# Schematic_v38.net
KiCad netlist of a schematic drawn in EAGLE
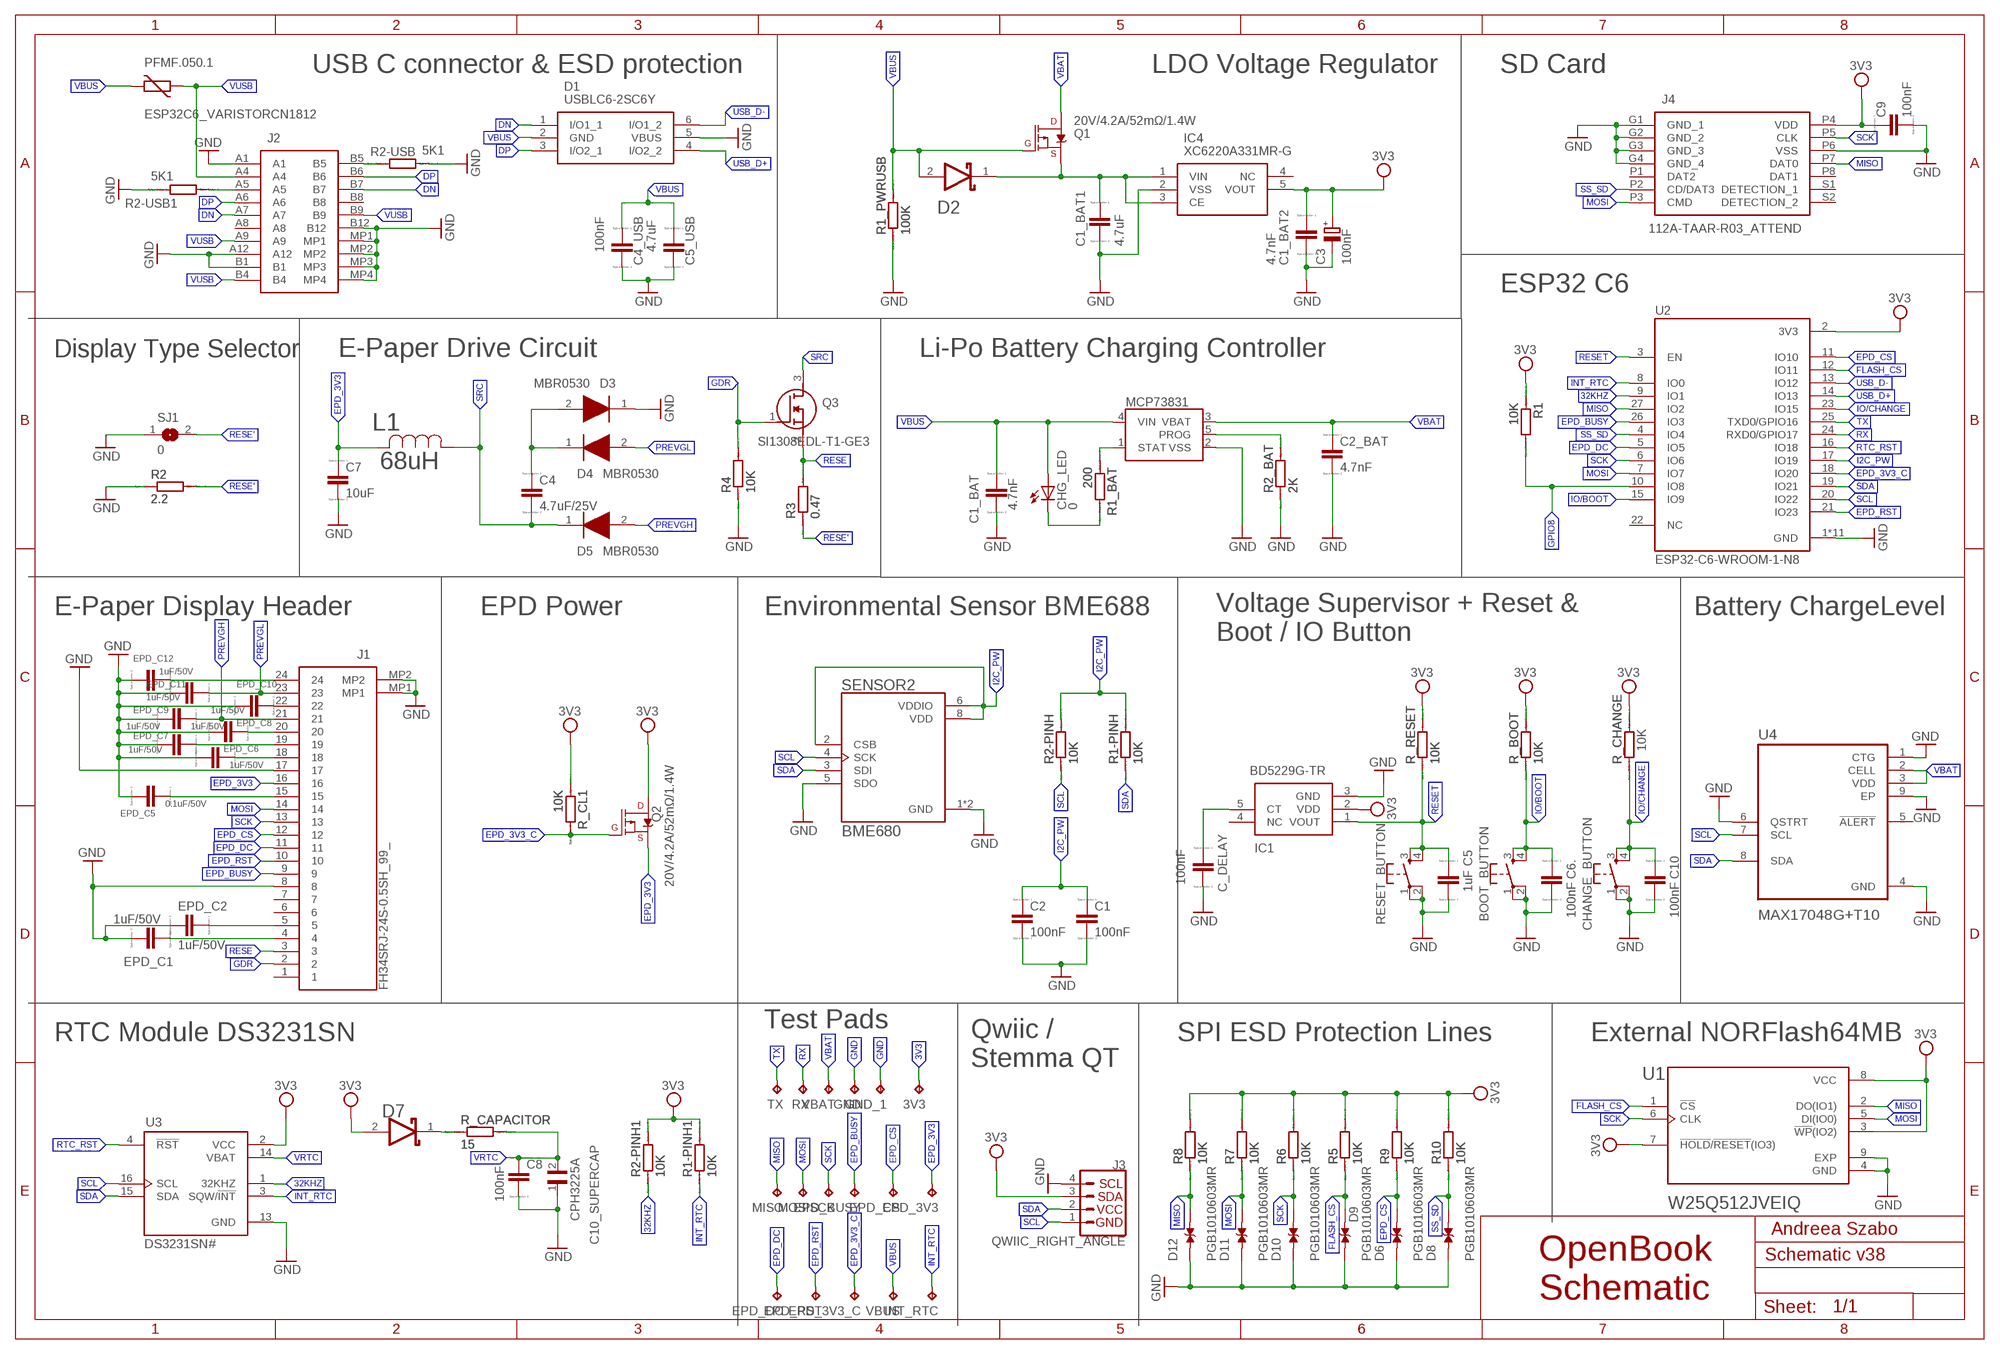
[diagram p0: schematic, sheet 1]

(export (version "E")
  (design (tool "Eeschema 10.0.6"))
  (components
    (comp (ref "3V3")
      (value "TPTP20R")
      (footprint "eagle-import:TP20R")
      (libsource (lib "eagle-import") (part "TPTP20R"))
    )
    (comp (ref "BOOT_BUTTON")
      (value "BUTTON_CUSYOMV1")
      (footprint "eagle-import:MYBUTTON")
      (libsource (lib "eagle-import") (part "BUTTON_CUSYOMV1"))
    )
    (comp (ref "C1")
      (value "100nF")
      (footprint "eagle-import:ESP32_WROVER_EAGLE-LTSPICE_C0402")
      (libsource (lib "eagle-import") (part "EAGLE-LTSPICE_CC0402"))
    )
    (comp (ref "C1_BAT")
      (value "4.7nF")
      (footprint "eagle-import:ESP32_WROVER_EAGLE-LTSPICE_C0402")
      (libsource (lib "eagle-import") (part "EAGLE-LTSPICE_CC0402"))
    )
    (comp (ref "C1_BAT1")
      (value "4.7uF")
      (footprint "eagle-import:ESP32_WROVER_EAGLE-LTSPICE_C0402")
      (libsource (lib "eagle-import") (part "EAGLE-LTSPICE_CC0402"))
    )
    (comp (ref "C1_BAT2")
      (value "4.7nF")
      (footprint "eagle-import:ESP32_WROVER_EAGLE-LTSPICE_C0402")
      (libsource (lib "eagle-import") (part "EAGLE-LTSPICE_CC0402"))
    )
    (comp (ref "C2")
      (value "100nF")
      (footprint "eagle-import:ESP32_WROVER_EAGLE-LTSPICE_C0402")
      (libsource (lib "eagle-import") (part "EAGLE-LTSPICE_CC0402"))
    )
    (comp (ref "C2_BAT")
      (value "4.7nF")
      (footprint "eagle-import:ESP32_WROVER_EAGLE-LTSPICE_C0402")
      (libsource (lib "eagle-import") (part "EAGLE-LTSPICE_CC0402"))
    )
    (comp (ref "C3")
      (value "100nF")
      (footprint "eagle-import:RCL_CT3528")
      (libsource (lib "eagle-import") (part "RCL_CPOL-EUCT3528"))
    )
    (comp (ref "C4")
      (value "4.7uF/25V")
      (footprint "eagle-import:ESP32_WROVER_EAGLE-LTSPICE_C0402")
      (libsource (lib "eagle-import") (part "EAGLE-LTSPICE_CC0402"))
    )
    (comp (ref "C4_USB")
      (value "100nF")
      (footprint "eagle-import:ESP32_WROVER_EAGLE-LTSPICE_C0402")
      (libsource (lib "eagle-import") (part "EAGLE-LTSPICE_CC0402"))
    )
    (comp (ref "C5")
      (value "1uF")
      (footprint "eagle-import:ESP32_WROVER_EAGLE-LTSPICE_C0402")
      (libsource (lib "eagle-import") (part "EAGLE-LTSPICE_CC0402"))
    )
    (comp (ref "C5_USB")
      (value "4.7uF")
      (footprint "eagle-import:ESP32_WROVER_EAGLE-LTSPICE_C0402")
      (libsource (lib "eagle-import") (part "EAGLE-LTSPICE_CC0402"))
    )
    (comp (ref "C6.")
      (value "100nF")
      (footprint "eagle-import:ESP32_WROVER_EAGLE-LTSPICE_C0402")
      (libsource (lib "eagle-import") (part "EAGLE-LTSPICE_CC0402"))
    )
    (comp (ref "C7")
      (value "10uF")
      (footprint "eagle-import:ESP32_WROVER_EAGLE-LTSPICE_C0402")
      (libsource (lib "eagle-import") (part "EAGLE-LTSPICE_CC0402"))
    )
    (comp (ref "C8")
      (value "100nF")
      (footprint "eagle-import:ESP32_WROVER_EAGLE-LTSPICE_C0402")
      (libsource (lib "eagle-import") (part "EAGLE-LTSPICE_CC0402"))
    )
    (comp (ref "C9")
      (value "100nF")
      (footprint "eagle-import:ESP32_WROVER_EAGLE-LTSPICE_C0402")
      (libsource (lib "eagle-import") (part "EAGLE-LTSPICE_CC0402"))
    )
    (comp (ref "C10")
      (value "100nF")
      (footprint "eagle-import:ESP32_WROVER_EAGLE-LTSPICE_C0402")
      (libsource (lib "eagle-import") (part "EAGLE-LTSPICE_CC0402"))
    )
    (comp (ref "C10_SUPERCAP")
      (value "CPH3225A")
      (footprint "eagle-import:CAPCP3225X100N")
      (fields (field (name "MF") "Seiko Instruments"))
      (libsource (lib "eagle-import") (part "CPH3225A"))
    )
    (comp (ref "CHANGE_BUTTON")
      (value "BUTTON_CUSYOMV1")
      (footprint "eagle-import:MYBUTTON")
      (libsource (lib "eagle-import") (part "BUTTON_CUSYOMV1"))
    )
    (comp (ref "CHG_LED")
      (value "0")
      (footprint "eagle-import:ADAFRUIT_CHIP-LED0603")
      (libsource (lib "eagle-import") (part "ADAFRUIT_LEDCHIP-LED0603"))
    )
    (comp (ref "C_DELAY")
      (value "100nF")
      (footprint "eagle-import:ESP32_WROVER_EAGLE-LTSPICE_C0402")
      (libsource (lib "eagle-import") (part "EAGLE-LTSPICE_CC0402"))
    )
    (comp (ref "D1")
      (value "USBLC6-2SC6Y")
      (footprint "eagle-import:SOT95P280X145-6N")
      (fields (field (name "MF") "STMicroelectronics"))
      (libsource (lib "eagle-import") (part "USBLC6-2SC6Y"))
    )
    (comp (ref "D2")
      (value "ESP32_WROVER_AVX---SD0805S020S1R0_AVX_SD0805S020S1R0_0_0AVX_SD0805S020S1R0_0_0")
      (footprint "eagle-import:ESP32_WROVER_AVX---SD0805S020S1R0_AVX_SD0805S020S1R0_0")
      (fields
        (field (name "DIGIKEY_PART_NUMBER") "478-7800-1-ND")
        (field (name "MF") "AVX")
        (field (name "MOUSER_PART_NUMBER") "581-SD0805S020S1R0")
      )
      (libsource (lib "eagle-import") (part "ESP32_WROVER_AVX---SD0805S020S1R0_AVX_SD0805S020S1R0_0_0AVX_SD0805S020S1R0_0_0"))
    )
    (comp (ref "D3")
      (value "MBR0530")
      (footprint "eagle-import:SOD3716X135N")
      (fields (field (name "MF") "ON Semiconductor"))
      (libsource (lib "eagle-import") (part "MBR0530"))
    )
    (comp (ref "D4")
      (value "MBR0530")
      (footprint "eagle-import:SOD3716X135N")
      (fields (field (name "MF") "ON Semiconductor"))
      (libsource (lib "eagle-import") (part "MBR0530"))
    )
    (comp (ref "D5")
      (value "MBR0530")
      (footprint "eagle-import:SOD3716X135N")
      (fields (field (name "MF") "ON Semiconductor"))
      (libsource (lib "eagle-import") (part "MBR0530"))
    )
    (comp (ref "D6")
      (value "PGB1010603MR")
      (footprint "eagle-import:DIOC1608X36N")
      (fields (field (name "MF") "Littelfuse Inc."))
      (libsource (lib "eagle-import") (part "PGB1010603MR"))
    )
    (comp (ref "D7")
      (value "SD0805S020S1R0")
      (footprint "eagle-import:ESP32_WROVER_AVX---SD0805S020S1R0_AVX_SD0805S020S1R0_0")
      (fields
        (field (name "DIGIKEY_PART_NUMBER") "478-7800-1-ND")
        (field (name "MF") "AVX")
        (field (name "MOUSER_PART_NUMBER") "581-SD0805S020S1R0")
      )
      (libsource (lib "eagle-import") (part "ESP32_WROVER_AVX---SD0805S020S1R0_AVX_SD0805S020S1R0_0_0AVX_SD0805S020S1R0_0_0"))
    )
    (comp (ref "D8")
      (value "PGB1010603MR")
      (footprint "eagle-import:DIOC1608X36N")
      (fields (field (name "MF") "Littelfuse Inc."))
      (libsource (lib "eagle-import") (part "PGB1010603MR"))
    )
    (comp (ref "D9")
      (value "PGB1010603MR")
      (footprint "eagle-import:DIOC1608X36N")
      (fields (field (name "MF") "Littelfuse Inc."))
      (libsource (lib "eagle-import") (part "PGB1010603MR"))
    )
    (comp (ref "D10")
      (value "PGB1010603MR")
      (footprint "eagle-import:DIOC1608X36N")
      (fields (field (name "MF") "Littelfuse Inc."))
      (libsource (lib "eagle-import") (part "PGB1010603MR"))
    )
    (comp (ref "D11")
      (value "PGB1010603MR")
      (footprint "eagle-import:DIOC1608X36N")
      (fields (field (name "MF") "Littelfuse Inc."))
      (libsource (lib "eagle-import") (part "PGB1010603MR"))
    )
    (comp (ref "D12")
      (value "PGB1010603MR")
      (footprint "eagle-import:DIOC1608X36N")
      (fields (field (name "MF") "Littelfuse Inc."))
      (libsource (lib "eagle-import") (part "PGB1010603MR"))
    )
    (comp (ref "EPD_3V3")
      (value "TPTP20R")
      (footprint "eagle-import:TP20R")
      (libsource (lib "eagle-import") (part "TPTP20R"))
    )
    (comp (ref "EPD_3V3_C")
      (value "TPTP20R")
      (footprint "eagle-import:TP20R")
      (libsource (lib "eagle-import") (part "TPTP20R"))
    )
    (comp (ref "EPD_BUSY")
      (value "TPTP20R")
      (footprint "eagle-import:TP20R")
      (libsource (lib "eagle-import") (part "TPTP20R"))
    )
    (comp (ref "EPD_C1")
      (value "1uF/50V")
      (footprint "eagle-import:ESP32_WROVER_EAGLE-LTSPICE_C0402")
      (libsource (lib "eagle-import") (part "EAGLE-LTSPICE_CC0402"))
    )
    (comp (ref "EPD_C2")
      (value "1uF/50V")
      (footprint "eagle-import:ESP32_WROVER_EAGLE-LTSPICE_C0402")
      (libsource (lib "eagle-import") (part "EAGLE-LTSPICE_CC0402"))
    )
    (comp (ref "EPD_C5")
      (value "0.1uF/50V")
      (footprint "eagle-import:ESP32_WROVER_EAGLE-LTSPICE_C0402")
      (libsource (lib "eagle-import") (part "EAGLE-LTSPICE_CC0402"))
    )
    (comp (ref "EPD_C6")
      (value "1uF/50V")
      (footprint "eagle-import:ESP32_WROVER_EAGLE-LTSPICE_C0402")
      (libsource (lib "eagle-import") (part "EAGLE-LTSPICE_CC0402"))
    )
    (comp (ref "EPD_C7")
      (value "1uF/50V")
      (footprint "eagle-import:ESP32_WROVER_EAGLE-LTSPICE_C0402")
      (libsource (lib "eagle-import") (part "EAGLE-LTSPICE_CC0402"))
    )
    (comp (ref "EPD_C8")
      (value "1uF/50V")
      (footprint "eagle-import:ESP32_WROVER_EAGLE-LTSPICE_C0402")
      (libsource (lib "eagle-import") (part "EAGLE-LTSPICE_CC0402"))
    )
    (comp (ref "EPD_C9")
      (value "1uF/50V")
      (footprint "eagle-import:ESP32_WROVER_EAGLE-LTSPICE_C0402")
      (libsource (lib "eagle-import") (part "EAGLE-LTSPICE_CC0402"))
    )
    (comp (ref "EPD_C10")
      (value "1uF/50V")
      (footprint "eagle-import:ESP32_WROVER_EAGLE-LTSPICE_C0402")
      (libsource (lib "eagle-import") (part "EAGLE-LTSPICE_CC0402"))
    )
    (comp (ref "EPD_C11")
      (value "1uF/50V")
      (footprint "eagle-import:ESP32_WROVER_EAGLE-LTSPICE_C0402")
      (libsource (lib "eagle-import") (part "EAGLE-LTSPICE_CC0402"))
    )
    (comp (ref "EPD_C12")
      (value "1uF/50V")
      (footprint "eagle-import:ESP32_WROVER_EAGLE-LTSPICE_C0402")
      (libsource (lib "eagle-import") (part "EAGLE-LTSPICE_CC0402"))
    )
    (comp (ref "EPD_CS")
      (value "TPTP20R")
      (footprint "eagle-import:TP20R")
      (libsource (lib "eagle-import") (part "TPTP20R"))
    )
    (comp (ref "EPD_DC")
      (value "TPTP20R")
      (footprint "eagle-import:TP20R")
      (libsource (lib "eagle-import") (part "TPTP20R"))
    )
    (comp (ref "EPD_RST")
      (value "TPTP20R")
      (footprint "eagle-import:TP20R")
      (libsource (lib "eagle-import") (part "TPTP20R"))
    )
    (comp (ref "GND")
      (value "TPTP20R")
      (footprint "eagle-import:TP20R")
      (libsource (lib "eagle-import") (part "TPTP20R"))
    )
    (comp (ref "GND_1")
      (value "TPTP20R")
      (footprint "eagle-import:TP20R")
      (libsource (lib "eagle-import") (part "TPTP20R"))
    )
    (comp (ref "IC1")
      (value "BD5229G-TR")
      (footprint "eagle-import:SOT95P280X125-5N")
      (fields (field (name "MOUSER_PART_NUMBER") "755-BD5229G-TR"))
      (libsource (lib "eagle-import") (part "BD5229G-TR"))
    )
    (comp (ref "IC4")
      (value "XC6220A331MR-G")
      (footprint "eagle-import:SOT95P280X120-5N")
      (fields (field (name "MOUSER_PART_NUMBER") "865-XC6220A331MR-G"))
      (libsource (lib "eagle-import") (part "XC6220A331MR-G"))
    )
    (comp (ref "INT_RTC")
      (value "TPTP20R")
      (footprint "eagle-import:TP20R")
      (libsource (lib "eagle-import") (part "TPTP20R"))
    )
    (comp (ref "J1")
      (value "FH34SRJ-24S-0.5SH_99_")
      (footprint "eagle-import:FH34SRJ24S05SH99")
      (fields
        (field (name "MANUFACTURER_PART_NUMBER") "FH34SRJ-24S-0.5SH(99)")
        (field (name "MOUSER_PART_NUMBER") "798-FH34SRJ24S05SH99")
      )
      (libsource (lib "eagle-import") (part "FH34SRJ-24S-0.5SH_99_"))
    )
    (comp (ref "J2")
      (value "SAMACSYS_PARTS_USB4110-GF-A")
      (footprint "eagle-import:SAMACSYS_PARTS_USB4110GFA")
      (fields
        (field (name "MANUFACTURER_PART_NUMBER") "USB4110-GF-A")
        (field (name "MOUSER_PART_NUMBER") "640-USB4110-GF-A")
      )
      (libsource (lib "eagle-import") (part "SAMACSYS_PARTS_USB4110-GF-A"))
    )
    (comp (ref "J3")
      (value "QWIIC_RIGHT_ANGLE")
      (footprint "eagle-import:JST04_1MM_RA")
      (libsource (lib "eagle-import") (part "QWIIC_CONNECTORJS-1MM"))
    )
    (comp (ref "J4")
      (value "112A-TAAR-R03_ATTEND")
      (footprint "eagle-import:112ATAARR03ATTEND")
      (fields (field (name "MANUFACTURER_PART_NUMBER") "112A-TAAR-R03 ATTEND"))
      (libsource (lib "eagle-import") (part "112A-TAAR-R03_ATTEND"))
    )
    (comp (ref "L1")
      (value "68uH")
      (footprint "eagle-import:IND_4828-WE-TPC_WRE")
      (fields
        (field (name "MANUFACTURER_PART_NUMBER") "744043680")
        (field (name "COPYRIGHT") "Copyright (C) 2024 Ultra Librarian. All rights reserved.")
      )
      (libsource (lib "eagle-import") (part "744043680IND_4828-WE-TPC_WRE"))
    )
    (comp (ref "MCP73831")
      (value "MCP73831")
      (footprint "eagle-import:ESP32_WROVER_SPARKFUN-IC-POWER_SOT23-5")
      (libsource (lib "eagle-import") (part "ESP32_WROVER_SPARKFUN-IC-POWER_MCP73831"))
    )
    (comp (ref "MISO")
      (value "TPTP20R")
      (footprint "eagle-import:TP20R")
      (libsource (lib "eagle-import") (part "TPTP20R"))
    )
    (comp (ref "MOSI")
      (value "TPTP20R")
      (footprint "eagle-import:TP20R")
      (libsource (lib "eagle-import") (part "TPTP20R"))
    )
    (comp (ref "PFMF.050.1")
      (value "ESP32C6_VARISTORCN1812")
      (footprint "eagle-import:ESP32C6_VARISTOR_CT_CN1812")
      (libsource (lib "eagle-import") (part "ESP32C6_VARISTORCN1812"))
    )
    (comp (ref "Q1")
      (value "20V/4.2A/52mΩ/1.4W")
      (footprint "eagle-import:ESP32_WROVER_SPARKFUN-DISCRETESEMI_SOT23-3")
      (libsource (lib "eagle-import") (part "ESP32_WROVER_SPARKFUN-DISCRETESEMI_MOSFET_PCH-DMG2305UX-7"))
    )
    (comp (ref "Q2")
      (value "20V/4.2A/52mΩ/1.4W")
      (footprint "eagle-import:ESP32_WROVER_SPARKFUN-DISCRETESEMI_SOT23-3")
      (libsource (lib "eagle-import") (part "ESP32_WROVER_SPARKFUN-DISCRETESEMI_MOSFET_PCH-DMG2305UX-7"))
    )
    (comp (ref "Q3")
      (value "SI1308EDL-T1-GE3")
      (footprint "eagle-import:SOT65P210X110-3N")
      (fields (field (name "MF") "Vishay Siliconix"))
      (libsource (lib "eagle-import") (part "SI1308EDL-T1-GE3"))
    )
    (comp (ref "R1")
      (value "10K")
      (footprint "eagle-import:ESP32_WROVER_EAGLE-LTSPICE_R0402")
      (libsource (lib "eagle-import") (part "ESP32_WROVER_EAGLE-LTSPICE_RR0402"))
    )
    (comp (ref "R1-PINH")
      (value "10K")
      (footprint "eagle-import:ESP32_WROVER_EAGLE-LTSPICE_R0402")
      (libsource (lib "eagle-import") (part "ESP32_WROVER_EAGLE-LTSPICE_RR0402"))
    )
    (comp (ref "R1-PINH1")
      (value "10K")
      (footprint "eagle-import:ESP32_WROVER_EAGLE-LTSPICE_R0402")
      (libsource (lib "eagle-import") (part "ESP32_WROVER_EAGLE-LTSPICE_RR0402"))
    )
    (comp (ref "R1_BAT")
      (value "200")
      (footprint "eagle-import:ESP32_WROVER_EAGLE-LTSPICE_R0402")
      (libsource (lib "eagle-import") (part "ESP32_WROVER_EAGLE-LTSPICE_RR0402"))
    )
    (comp (ref "R1_PWRUSB")
      (value "100K")
      (footprint "eagle-import:ESP32_WROVER_EAGLE-LTSPICE_R0402")
      (libsource (lib "eagle-import") (part "ESP32_WROVER_EAGLE-LTSPICE_RR0402"))
    )
    (comp (ref "R2")
      (value "2.2")
      (footprint "eagle-import:ESP32_WROVER_EAGLE-LTSPICE_R0402")
      (libsource (lib "eagle-import") (part "ESP32_WROVER_EAGLE-LTSPICE_RR0402"))
    )
    (comp (ref "R2-PINH")
      (value "10K")
      (footprint "eagle-import:ESP32_WROVER_EAGLE-LTSPICE_R0402")
      (libsource (lib "eagle-import") (part "ESP32_WROVER_EAGLE-LTSPICE_RR0402"))
    )
    (comp (ref "R2-PINH1")
      (value "10K")
      (footprint "eagle-import:ESP32_WROVER_EAGLE-LTSPICE_R0402")
      (libsource (lib "eagle-import") (part "ESP32_WROVER_EAGLE-LTSPICE_RR0402"))
    )
    (comp (ref "R2-USB")
      (value "5K1")
      (footprint "eagle-import:ESP32_WROVER_EAGLE-LTSPICE_R0402")
      (libsource (lib "eagle-import") (part "ESP32_WROVER_EAGLE-LTSPICE_RR0402"))
    )
    (comp (ref "R2-USB1")
      (value "5K1")
      (footprint "eagle-import:ESP32_WROVER_EAGLE-LTSPICE_R0402")
      (libsource (lib "eagle-import") (part "ESP32_WROVER_EAGLE-LTSPICE_RR0402"))
    )
    (comp (ref "R2_BAT")
      (value "2K")
      (footprint "eagle-import:ESP32_WROVER_EAGLE-LTSPICE_R0402")
      (libsource (lib "eagle-import") (part "ESP32_WROVER_EAGLE-LTSPICE_RR0402"))
    )
    (comp (ref "R3")
      (value "0.47")
      (footprint "eagle-import:ESP32_WROVER_EAGLE-LTSPICE_R0402")
      (libsource (lib "eagle-import") (part "ESP32_WROVER_EAGLE-LTSPICE_RR0402"))
    )
    (comp (ref "R4")
      (value "10K")
      (footprint "eagle-import:ESP32_WROVER_EAGLE-LTSPICE_R0402")
      (libsource (lib "eagle-import") (part "ESP32_WROVER_EAGLE-LTSPICE_RR0402"))
    )
    (comp (ref "R5")
      (value "10K")
      (footprint "eagle-import:ESP32_WROVER_EAGLE-LTSPICE_R0402")
      (libsource (lib "eagle-import") (part "ESP32_WROVER_EAGLE-LTSPICE_RR0402"))
    )
    (comp (ref "R6")
      (value "10K")
      (footprint "eagle-import:ESP32_WROVER_EAGLE-LTSPICE_R0402")
      (libsource (lib "eagle-import") (part "ESP32_WROVER_EAGLE-LTSPICE_RR0402"))
    )
    (comp (ref "R7")
      (value "10K")
      (footprint "eagle-import:ESP32_WROVER_EAGLE-LTSPICE_R0402")
      (libsource (lib "eagle-import") (part "ESP32_WROVER_EAGLE-LTSPICE_RR0402"))
    )
    (comp (ref "R8")
      (value "10K")
      (footprint "eagle-import:ESP32_WROVER_EAGLE-LTSPICE_R0402")
      (libsource (lib "eagle-import") (part "ESP32_WROVER_EAGLE-LTSPICE_RR0402"))
    )
    (comp (ref "R9")
      (value "10K")
      (footprint "eagle-import:ESP32_WROVER_EAGLE-LTSPICE_R0402")
      (libsource (lib "eagle-import") (part "ESP32_WROVER_EAGLE-LTSPICE_RR0402"))
    )
    (comp (ref "R10")
      (value "10K")
      (footprint "eagle-import:ESP32_WROVER_EAGLE-LTSPICE_R0402")
      (libsource (lib "eagle-import") (part "ESP32_WROVER_EAGLE-LTSPICE_RR0402"))
    )
    (comp (ref "RESET_BUTTON")
      (value "BUTTON_CUSYOMV1")
      (footprint "eagle-import:MYBUTTON")
      (libsource (lib "eagle-import") (part "BUTTON_CUSYOMV1"))
    )
    (comp (ref "RX")
      (value "TPTP20R")
      (footprint "eagle-import:TP20R")
      (libsource (lib "eagle-import") (part "TPTP20R"))
    )
    (comp (ref "R_BOOT")
      (value "10K")
      (footprint "eagle-import:ESP32_WROVER_EAGLE-LTSPICE_R0402")
      (libsource (lib "eagle-import") (part "ESP32_WROVER_EAGLE-LTSPICE_RR0402"))
    )
    (comp (ref "R_CAPACITOR")
      (value "15")
      (footprint "eagle-import:ESP32_WROVER_EAGLE-LTSPICE_R0402")
      (libsource (lib "eagle-import") (part "ESP32_WROVER_EAGLE-LTSPICE_RR0402"))
    )
    (comp (ref "R_CHANGE")
      (value "10K")
      (footprint "eagle-import:ESP32_WROVER_EAGLE-LTSPICE_R0402")
      (libsource (lib "eagle-import") (part "ESP32_WROVER_EAGLE-LTSPICE_RR0402"))
    )
    (comp (ref "R_CL1")
      (value "10K")
      (footprint "eagle-import:ESP32_WROVER_EAGLE-LTSPICE_R0402")
      (libsource (lib "eagle-import") (part "ESP32_WROVER_EAGLE-LTSPICE_RR0402"))
    )
    (comp (ref "R_RESET")
      (value "10K")
      (footprint "eagle-import:ESP32_WROVER_EAGLE-LTSPICE_R0402")
      (libsource (lib "eagle-import") (part "ESP32_WROVER_EAGLE-LTSPICE_RR0402"))
    )
    (comp (ref "SCK")
      (value "TPTP20R")
      (footprint "eagle-import:TP20R")
      (libsource (lib "eagle-import") (part "TPTP20R"))
    )
    (comp (ref "SENSOR2")
      (value "BME680")
      (footprint "eagle-import:ESP32_WROVER_BME680_PSON80P300X300X100-8N")
      (fields (field (name "MF") "Bosch Sensortec"))
      (libsource (lib "eagle-import") (part "ESP32_WROVER_BME680_BME680"))
    )
    (comp (ref "SJ1") (value "0") (footprint "eagle-import:SJ") (libsource (lib "eagle-import") (part "SJ")))
    (comp (ref "TX")
      (value "TPTP20R")
      (footprint "eagle-import:TP20R")
      (libsource (lib "eagle-import") (part "TPTP20R"))
    )
    (comp (ref "U1")
      (value "W25Q512JVEIQ")
      (footprint "eagle-import:SON127P600X800X80-9N")
      (fields (field (name "MF") "Winbond Electronics"))
      (libsource (lib "eagle-import") (part "W25Q512JVEIQ"))
    )
    (comp (ref "U2")
      (value "ESP32-C6-WROOM-1-N8")
      (footprint "eagle-import:XCVR_ESP32-C6-WROOM-1-N8")
      (fields (field (name "MF") "Espressif Systems"))
      (libsource (lib "eagle-import") (part "ESP32-C6-WROOM-1-N8"))
    )
    (comp (ref "U3")
      (value "DS3231SN#")
      (footprint "eagle-import:SOIC127P1032X265-16N")
      (fields (field (name "MF") "Analog Devices"))
      (libsource (lib "eagle-import") (part "DS3231SN#"))
    )
    (comp (ref "U4")
      (value "MAX17048G+T10")
      (footprint "eagle-import:SON50P200X200X80-9N")
      (fields (field (name "MF") "Analog Devices"))
      (libsource (lib "eagle-import") (part "MAX17048G+T10"))
    )
    (comp (ref "VBAT")
      (value "TPTP20R")
      (footprint "eagle-import:TP20R")
      (libsource (lib "eagle-import") (part "TPTP20R"))
    )
    (comp (ref "VBUS")
      (value "TPTP20R")
      (footprint "eagle-import:TP20R")
      (libsource (lib "eagle-import") (part "TPTP20R"))
    )
  )
  (nets
    (net (code "1") (name "3V3") (class "Default")
      (node (ref "3V3") (pin "TP") (pinfunction "TP_TP") (pintype "input"))
      (node (ref "C1_BAT2") (pin "1") (pinfunction "1_1") (pintype "passive"))
      (node (ref "C3") (pin "+") (pinfunction "+_+") (pintype "passive"))
      (node (ref "C9") (pin "1") (pinfunction "1_1") (pintype "passive"))
      (node (ref "D7") (pin "2") (pinfunction "ANODE_2") (pintype "bidirectional"))
      (node (ref "IC1") (pin "2") (pinfunction "VDD_2") (pintype "bidirectional"))
      (node (ref "IC4") (pin "5") (pinfunction "VOUT_5") (pintype "bidirectional"))
      (node (ref "J3") (pin "3") (pinfunction "3_3") (pintype "passive"))
      (node (ref "J4") (pin "P4") (pinfunction "VDD_P4") (pintype "bidirectional"))
      (node (ref "Q2") (pin "3") (pinfunction "D_3") (pintype "bidirectional"))
      (node (ref "R1") (pin "1") (pinfunction "1_1") (pintype "passive"))
      (node (ref "R1-PINH1") (pin "2") (pinfunction "2_2") (pintype "passive"))
      (node (ref "R10") (pin "2") (pinfunction "2_2") (pintype "passive"))
      (node (ref "R2-PINH1") (pin "2") (pinfunction "2_2") (pintype "passive"))
      (node (ref "R5") (pin "2") (pinfunction "2_2") (pintype "passive"))
      (node (ref "R6") (pin "2") (pinfunction "2_2") (pintype "passive"))
      (node (ref "R7") (pin "2") (pinfunction "2_2") (pintype "passive"))
      (node (ref "R8") (pin "2") (pinfunction "2_2") (pintype "passive"))
      (node (ref "R9") (pin "2") (pinfunction "2_2") (pintype "passive"))
      (node (ref "R_BOOT") (pin "2") (pinfunction "2_2") (pintype "passive"))
      (node (ref "R_CHANGE") (pin "2") (pinfunction "2_2") (pintype "passive"))
      (node (ref "R_CL1") (pin "1") (pinfunction "1_1") (pintype "passive"))
      (node (ref "R_RESET") (pin "2") (pinfunction "2_2") (pintype "passive"))
      (node (ref "U1") (pin "3") (pinfunction "~{WP}(IO2)_3") (pintype "bidirectional"))
      (node (ref "U1") (pin "7") (pinfunction "~{HOLD}/~{RESET}(IO3)_7") (pintype "bidirectional"))
      (node (ref "U1") (pin "8") (pinfunction "VCC_8") (pintype "power_in"))
      (node (ref "U2") (pin "2") (pinfunction "3V3_2") (pintype "power_in"))
      (node (ref "U3") (pin "2") (pinfunction "VCC_2") (pintype "power_in"))
    )
    (net (code "2") (name "32KHZ") (class "Default")
      (node (ref "R2-PINH1") (pin "1") (pinfunction "1_1") (pintype "passive"))
      (node (ref "U2") (pin "9") (pinfunction "IO1_9") (pintype "bidirectional"))
      (node (ref "U3") (pin "1") (pinfunction "32KHZ_1") (pintype "output"))
    )
    (net (code "3") (name "DN") (class "Default")
      (node (ref "D1") (pin "1") (pinfunction "I/O1_1_1") (pintype "bidirectional"))
      (node (ref "J2") (pin "A7") (pinfunction "A7_A7") (pintype "bidirectional"))
      (node (ref "J2") (pin "B7") (pinfunction "B7_B7") (pintype "bidirectional"))
    )
    (net (code "4") (name "DP") (class "Default")
      (node (ref "D1") (pin "3") (pinfunction "I/O2_1_3") (pintype "bidirectional"))
      (node (ref "J2") (pin "A6") (pinfunction "A6_A6") (pintype "bidirectional"))
      (node (ref "J2") (pin "B6") (pinfunction "B6_B6") (pintype "bidirectional"))
    )
    (net (code "5") (name "EPD_3V3") (class "Default")
      (node (ref "C7") (pin "1") (pinfunction "1_1") (pintype "passive"))
      (node (ref "EPD_3V3") (pin "TP") (pinfunction "TP_TP") (pintype "input"))
      (node (ref "J1") (pin "16") (pinfunction "16_16") (pintype "bidirectional"))
      (node (ref "L1") (pin "2") (pinfunction "2_2") (pintype "passive"))
      (node (ref "Q2") (pin "2") (pinfunction "S_2") (pintype "bidirectional"))
    )
    (net (code "6") (name "EPD_3V3_C") (class "Default")
      (node (ref "EPD_3V3_C") (pin "TP") (pinfunction "TP_TP") (pintype "input"))
      (node (ref "Q2") (pin "1") (pinfunction "G_1") (pintype "bidirectional"))
      (node (ref "R_CL1") (pin "2") (pinfunction "2_2") (pintype "passive"))
      (node (ref "U2") (pin "18") (pinfunction "IO20_18") (pintype "bidirectional"))
    )
    (net (code "7") (name "EPD_BUSY") (class "Default")
      (node (ref "EPD_BUSY") (pin "TP") (pinfunction "TP_TP") (pintype "input"))
      (node (ref "J1") (pin "9") (pinfunction "9_9") (pintype "bidirectional"))
      (node (ref "U2") (pin "26") (pinfunction "IO3_26") (pintype "bidirectional"))
    )
    (net (code "8") (name "EPD_CS") (class "Default")
      (node (ref "D6") (pin "2") (pinfunction "2_2") (pintype "passive"))
      (node (ref "EPD_CS") (pin "TP") (pinfunction "TP_TP") (pintype "input"))
      (node (ref "J1") (pin "12") (pinfunction "12_12") (pintype "bidirectional"))
      (node (ref "R9") (pin "1") (pinfunction "1_1") (pintype "passive"))
      (node (ref "U2") (pin "11") (pinfunction "IO10_11") (pintype "bidirectional"))
    )
    (net (code "9") (name "EPD_DC") (class "Default")
      (node (ref "EPD_DC") (pin "TP") (pinfunction "TP_TP") (pintype "input"))
      (node (ref "J1") (pin "11") (pinfunction "11_11") (pintype "bidirectional"))
      (node (ref "U2") (pin "5") (pinfunction "IO5_5") (pintype "bidirectional"))
    )
    (net (code "10") (name "EPD_RST") (class "Default")
      (node (ref "EPD_RST") (pin "TP") (pinfunction "TP_TP") (pintype "input"))
      (node (ref "J1") (pin "10") (pinfunction "10_10") (pintype "bidirectional"))
      (node (ref "U2") (pin "21") (pinfunction "IO23_21") (pintype "bidirectional"))
    )
    (net (code "11") (name "FLASH_CS") (class "Default")
      (node (ref "D9") (pin "2") (pinfunction "2_2") (pintype "passive"))
      (node (ref "R5") (pin "1") (pinfunction "1_1") (pintype "passive"))
      (node (ref "U1") (pin "1") (pinfunction "~{CS}_1") (pintype "input"))
      (node (ref "U2") (pin "12") (pinfunction "IO11_12") (pintype "bidirectional"))
    )
    (net (code "12") (name "GDR") (class "Default")
      (node (ref "J1") (pin "2") (pinfunction "2_2") (pintype "bidirectional"))
      (node (ref "Q3") (pin "1") (pinfunction "G_1") (pintype "bidirectional"))
      (node (ref "R4") (pin "2") (pinfunction "2_2") (pintype "passive"))
    )
    (net (code "13") (name "GND") (class "Default")
      (node (ref "BOOT_BUTTON") (pin "1") (pinfunction "1_1") (pintype "passive"))
      (node (ref "BOOT_BUTTON") (pin "2") (pinfunction "2_2") (pintype "passive"))
      (node (ref "C1") (pin "2") (pinfunction "2_2") (pintype "passive"))
      (node (ref "C10") (pin "2") (pinfunction "2_2") (pintype "passive"))
      (node (ref "C10_SUPERCAP") (pin "1") (pinfunction "1_1") (pintype "passive"))
      (node (ref "C1_BAT") (pin "2") (pinfunction "2_2") (pintype "passive"))
      (node (ref "C1_BAT1") (pin "2") (pinfunction "2_2") (pintype "passive"))
      (node (ref "C1_BAT2") (pin "2") (pinfunction "2_2") (pintype "passive"))
      (node (ref "C2") (pin "2") (pinfunction "2_2") (pintype "passive"))
      (node (ref "C2_BAT") (pin "2") (pinfunction "2_2") (pintype "passive"))
      (node (ref "C3") (pin "-") (pinfunction "-_-") (pintype "passive"))
      (node (ref "C4_USB") (pin "2") (pinfunction "2_2") (pintype "passive"))
      (node (ref "C5") (pin "2") (pinfunction "2_2") (pintype "passive"))
      (node (ref "C5_USB") (pin "2") (pinfunction "2_2") (pintype "passive"))
      (node (ref "C6.") (pin "2") (pinfunction "2_2") (pintype "passive"))
      (node (ref "C7") (pin "2") (pinfunction "2_2") (pintype "passive"))
      (node (ref "C8") (pin "2") (pinfunction "2_2") (pintype "passive"))
      (node (ref "C9") (pin "2") (pinfunction "2_2") (pintype "passive"))
      (node (ref "CHANGE_BUTTON") (pin "1") (pinfunction "1_1") (pintype "passive"))
      (node (ref "CHANGE_BUTTON") (pin "2") (pinfunction "2_2") (pintype "passive"))
      (node (ref "C_DELAY") (pin "2") (pinfunction "2_2") (pintype "passive"))
      (node (ref "D1") (pin "5") (pinfunction "VBUS_5") (pintype "bidirectional"))
      (node (ref "D10") (pin "1") (pinfunction "1_1") (pintype "passive"))
      (node (ref "D11") (pin "1") (pinfunction "1_1") (pintype "passive"))
      (node (ref "D12") (pin "1") (pinfunction "1_1") (pintype "passive"))
      (node (ref "D3") (pin "1") (pinfunction "K_1") (pintype "bidirectional"))
      (node (ref "D6") (pin "1") (pinfunction "1_1") (pintype "passive"))
      (node (ref "D8") (pin "1") (pinfunction "1_1") (pintype "passive"))
      (node (ref "D9") (pin "1") (pinfunction "1_1") (pintype "passive"))
      (node (ref "EPD_C1") (pin "2") (pinfunction "2_2") (pintype "passive"))
      (node (ref "EPD_C10") (pin "2") (pinfunction "2_2") (pintype "passive"))
      (node (ref "EPD_C11") (pin "2") (pinfunction "2_2") (pintype "passive"))
      (node (ref "EPD_C12") (pin "2") (pinfunction "2_2") (pintype "passive"))
      (node (ref "EPD_C2") (pin "2") (pinfunction "2_2") (pintype "passive"))
      (node (ref "EPD_C5") (pin "2") (pinfunction "2_2") (pintype "passive"))
      (node (ref "EPD_C6") (pin "2") (pinfunction "2_2") (pintype "passive"))
      (node (ref "EPD_C7") (pin "2") (pinfunction "2_2") (pintype "passive"))
      (node (ref "EPD_C8") (pin "2") (pinfunction "2_2") (pintype "passive"))
      (node (ref "EPD_C9") (pin "2") (pinfunction "2_2") (pintype "passive"))
      (node (ref "GND") (pin "TP") (pinfunction "TP_TP") (pintype "input"))
      (node (ref "GND_1") (pin "TP") (pinfunction "TP_TP") (pintype "input"))
      (node (ref "IC1") (pin "3") (pinfunction "GND_3") (pintype "bidirectional"))
      (node (ref "IC4") (pin "2") (pinfunction "VSS_2") (pintype "bidirectional"))
      (node (ref "J1") (pin "17") (pinfunction "17_17") (pintype "bidirectional"))
      (node (ref "J1") (pin "8") (pinfunction "8_8") (pintype "bidirectional"))
      (node (ref "J1") (pin "MP1") (pinfunction "MP1_MP1") (pintype "bidirectional"))
      (node (ref "J1") (pin "MP2") (pinfunction "MP2_MP2") (pintype "bidirectional"))
      (node (ref "J2") (pin "A1") (pinfunction "A1_A1") (pintype "bidirectional"))
      (node (ref "J2") (pin "A12") (pinfunction "A12_A12") (pintype "bidirectional"))
      (node (ref "J2") (pin "B1") (pinfunction "B1_B1") (pintype "bidirectional"))
      (node (ref "J2") (pin "B12") (pinfunction "B12_B12") (pintype "bidirectional"))
      (node (ref "J2") (pin "MP1") (pinfunction "MP1_MP1") (pintype "bidirectional"))
      (node (ref "J2") (pin "MP2") (pinfunction "MP2_MP2") (pintype "bidirectional"))
      (node (ref "J2") (pin "MP3") (pinfunction "MP3_MP3") (pintype "bidirectional"))
      (node (ref "J2") (pin "MP4") (pinfunction "MP4_MP4") (pintype "bidirectional"))
      (node (ref "J3") (pin "4") (pinfunction "4_4") (pintype "passive"))
      (node (ref "J4") (pin "G1") (pinfunction "GND_1_G1") (pintype "bidirectional"))
      (node (ref "J4") (pin "G2") (pinfunction "GND_2_G2") (pintype "bidirectional"))
      (node (ref "J4") (pin "G3") (pinfunction "GND_3_G3") (pintype "bidirectional"))
      (node (ref "J4") (pin "G4") (pinfunction "GND_4_G4") (pintype "bidirectional"))
      (node (ref "J4") (pin "P6") (pinfunction "VSS_P6") (pintype "bidirectional"))
      (node (ref "MCP73831") (pin "2") (pinfunction "VSS_2") (pintype "power_in"))
      (node (ref "R1_PWRUSB") (pin "1") (pinfunction "1_1") (pintype "passive"))
      (node (ref "R2") (pin "1") (pinfunction "1_1") (pintype "passive"))
      (node (ref "R2-USB") (pin "2") (pinfunction "2_2") (pintype "passive"))
      (node (ref "R2-USB1") (pin "1") (pinfunction "1_1") (pintype "passive"))
      (node (ref "R2_BAT") (pin "1") (pinfunction "1_1") (pintype "passive"))
      (node (ref "R4") (pin "1") (pinfunction "1_1") (pintype "passive"))
      (node (ref "RESET_BUTTON") (pin "1") (pinfunction "1_1") (pintype "passive"))
      (node (ref "RESET_BUTTON") (pin "2") (pinfunction "2_2") (pintype "passive"))
      (node (ref "SENSOR2") (pin "1") (pinfunction "GND_1") (pintype "power_in"))
      (node (ref "SENSOR2") (pin "5") (pinfunction "SDO_5") (pintype "bidirectional"))
      (node (ref "SENSOR2") (pin "7") (pinfunction "GND_7") (pintype "power_in"))
      (node (ref "SJ1") (pin "1") (pinfunction "1_1") (pintype "passive"))
      (node (ref "U1") (pin "4") (pinfunction "GND_4") (pintype "power_in"))
      (node (ref "U1") (pin "9") (pinfunction "EXP_9") (pintype "passive"))
      (node (ref "U2") (pin "1") (pinfunction "GND_1") (pintype "power_in"))
      (node (ref "U2") (pin "28") (pinfunction "GND_28") (pintype "power_in"))
      (node (ref "U2") (pin "29_1") (pinfunction "GND_29_1") (pintype "power_in"))
      (node (ref "U2") (pin "29_2") (pinfunction "GND_29_2") (pintype "power_in"))
      (node (ref "U2") (pin "29_3") (pinfunction "GND_29_3") (pintype "power_in"))
      (node (ref "U2") (pin "29_4") (pinfunction "GND_29_4") (pintype "power_in"))
      (node (ref "U2") (pin "29_5") (pinfunction "GND_29_5") (pintype "power_in"))
      (node (ref "U2") (pin "29_6") (pinfunction "GND_29_6") (pintype "power_in"))
      (node (ref "U2") (pin "29_7") (pinfunction "GND_29_7") (pintype "power_in"))
      (node (ref "U2") (pin "29_8") (pinfunction "GND_29_8") (pintype "power_in"))
      (node (ref "U2") (pin "29_9") (pinfunction "GND_29_9") (pintype "power_in"))
      (node (ref "U3") (pin "13") (pinfunction "GND_13") (pintype "power_in"))
      (node (ref "U4") (pin "1") (pinfunction "CTG_1") (pintype "power_in"))
      (node (ref "U4") (pin "4") (pinfunction "GND_4") (pintype "power_in"))
      (node (ref "U4") (pin "6") (pinfunction "QSTRT_6") (pintype "input"))
      (node (ref "U4") (pin "9") (pinfunction "EP_9") (pintype "power_in"))
    )
    (net (code "14") (name "GPIO8") (class "Default")
      (node (ref "R1") (pin "2") (pinfunction "2_2") (pintype "passive"))
      (node (ref "U2") (pin "10") (pinfunction "IO8_10") (pintype "bidirectional"))
    )
    (net (code "15") (name "I2C_PW") (class "Default")
      (node (ref "C1") (pin "1") (pinfunction "1_1") (pintype "passive"))
      (node (ref "C2") (pin "1") (pinfunction "1_1") (pintype "passive"))
      (node (ref "R1-PINH") (pin "2") (pinfunction "2_2") (pintype "passive"))
      (node (ref "R2-PINH") (pin "2") (pinfunction "2_2") (pintype "passive"))
      (node (ref "SENSOR2") (pin "2") (pinfunction "CSB_2") (pintype "input"))
      (node (ref "SENSOR2") (pin "6") (pinfunction "VDDIO_6") (pintype "power_in"))
      (node (ref "SENSOR2") (pin "8") (pinfunction "VDD_8") (pintype "power_in"))
      (node (ref "U2") (pin "17") (pinfunction "IO19_17") (pintype "bidirectional"))
    )
    (net (code "16") (name "INT_RTC") (class "Default")
      (node (ref "INT_RTC") (pin "TP") (pinfunction "TP_TP") (pintype "input"))
      (node (ref "R1-PINH1") (pin "1") (pinfunction "1_1") (pintype "passive"))
      (node (ref "U2") (pin "8") (pinfunction "IO0_8") (pintype "bidirectional"))
      (node (ref "U3") (pin "3") (pinfunction "SQW/~{INT}_3") (pintype "output"))
    )
    (net (code "17") (name "IO{slash}BOOT") (class "Default")
      (node (ref "BOOT_BUTTON") (pin "3") (pinfunction "3_3") (pintype "passive"))
      (node (ref "BOOT_BUTTON") (pin "4") (pinfunction "4_4") (pintype "passive"))
      (node (ref "C6.") (pin "1") (pinfunction "1_1") (pintype "passive"))
      (node (ref "R_BOOT") (pin "1") (pinfunction "1_1") (pintype "passive"))
      (node (ref "U2") (pin "15") (pinfunction "IO9_15") (pintype "bidirectional"))
    )
    (net (code "18") (name "IO{slash}CHANGE") (class "Default")
      (node (ref "C10") (pin "1") (pinfunction "1_1") (pintype "passive"))
      (node (ref "CHANGE_BUTTON") (pin "3") (pinfunction "3_3") (pintype "passive"))
      (node (ref "CHANGE_BUTTON") (pin "4") (pinfunction "4_4") (pintype "passive"))
      (node (ref "R_CHANGE") (pin "1") (pinfunction "1_1") (pintype "passive"))
      (node (ref "U2") (pin "23") (pinfunction "IO15_23") (pintype "bidirectional"))
    )
    (net (code "19") (name "MISO") (class "Default")
      (node (ref "D12") (pin "2") (pinfunction "2_2") (pintype "passive"))
      (node (ref "J4") (pin "P7") (pinfunction "DAT0_P7") (pintype "bidirectional"))
      (node (ref "MISO") (pin "TP") (pinfunction "TP_TP") (pintype "input"))
      (node (ref "R8") (pin "1") (pinfunction "1_1") (pintype "passive"))
      (node (ref "U1") (pin "2") (pinfunction "DO(IO1)_2") (pintype "bidirectional"))
      (node (ref "U2") (pin "27") (pinfunction "IO2_27") (pintype "bidirectional"))
    )
    (net (code "20") (name "MOSI") (class "Default")
      (node (ref "D11") (pin "2") (pinfunction "2_2") (pintype "passive"))
      (node (ref "J1") (pin "14") (pinfunction "14_14") (pintype "bidirectional"))
      (node (ref "J4") (pin "P3") (pinfunction "CMD_P3") (pintype "bidirectional"))
      (node (ref "MOSI") (pin "TP") (pinfunction "TP_TP") (pintype "input"))
      (node (ref "R7") (pin "1") (pinfunction "1_1") (pintype "passive"))
      (node (ref "U1") (pin "5") (pinfunction "DI(IO0)_5") (pintype "bidirectional"))
      (node (ref "U2") (pin "7") (pinfunction "IO7_7") (pintype "bidirectional"))
    )
    (net (code "21") (name "Net-(CHG_LED-PadC)") (class "Default")
      (node (ref "CHG_LED") (pin "C") (pinfunction "C_C") (pintype "passive"))
      (node (ref "R1_BAT") (pin "2") (pinfunction "2_2") (pintype "passive"))
    )
    (net (code "22") (name "Net-(D2-CATHODE)") (class "Default")
      (node (ref "C1_BAT1") (pin "1") (pinfunction "1_1") (pintype "passive"))
      (node (ref "D2") (pin "1") (pinfunction "CATHODE_1") (pintype "bidirectional"))
      (node (ref "IC4") (pin "1") (pinfunction "VIN_1") (pintype "bidirectional"))
      (node (ref "IC4") (pin "3") (pinfunction "CE_3") (pintype "bidirectional"))
      (node (ref "Q1") (pin "2") (pinfunction "S_2") (pintype "bidirectional"))
    )
    (net (code "23") (name "Net-(D3-A)") (class "Default")
      (node (ref "C4") (pin "1") (pinfunction "1_1") (pintype "passive"))
      (node (ref "D3") (pin "2") (pinfunction "A_2") (pintype "bidirectional"))
      (node (ref "D4") (pin "1") (pinfunction "K_1") (pintype "bidirectional"))
    )
    (net (code "24") (name "Net-(D7-CATHODE)") (class "Default")
      (node (ref "D7") (pin "1") (pinfunction "CATHODE_1") (pintype "bidirectional"))
      (node (ref "R_CAPACITOR") (pin "1") (pinfunction "1_1") (pintype "passive"))
    )
    (net (code "25") (name "Net-(EPD_C1-Pad1)") (class "Default")
      (node (ref "EPD_C1") (pin "1") (pinfunction "1_1") (pintype "passive"))
      (node (ref "J1") (pin "4") (pinfunction "4_4") (pintype "bidirectional"))
    )
    (net (code "26") (name "Net-(EPD_C2-Pad1)") (class "Default")
      (node (ref "EPD_C2") (pin "1") (pinfunction "1_1") (pintype "passive"))
      (node (ref "J1") (pin "5") (pinfunction "5_5") (pintype "bidirectional"))
    )
    (net (code "27") (name "Net-(EPD_C5-Pad1)") (class "Default")
      (node (ref "EPD_C5") (pin "1") (pinfunction "1_1") (pintype "passive"))
      (node (ref "J1") (pin "15") (pinfunction "15_15") (pintype "bidirectional"))
    )
    (net (code "28") (name "Net-(EPD_C6-Pad1)") (class "Default")
      (node (ref "EPD_C6") (pin "1") (pinfunction "1_1") (pintype "passive"))
      (node (ref "J1") (pin "18") (pinfunction "18_18") (pintype "bidirectional"))
    )
    (net (code "29") (name "Net-(EPD_C7-Pad1)") (class "Default")
      (node (ref "EPD_C7") (pin "1") (pinfunction "1_1") (pintype "passive"))
      (node (ref "J1") (pin "19") (pinfunction "19_19") (pintype "bidirectional"))
    )
    (net (code "30") (name "Net-(EPD_C8-Pad1)") (class "Default")
      (node (ref "EPD_C8") (pin "1") (pinfunction "1_1") (pintype "passive"))
      (node (ref "J1") (pin "20") (pinfunction "20_20") (pintype "bidirectional"))
    )
    (net (code "31") (name "Net-(EPD_C10-Pad1)") (class "Default")
      (node (ref "EPD_C10") (pin "1") (pinfunction "1_1") (pintype "passive"))
      (node (ref "J1") (pin "22") (pinfunction "22_22") (pintype "bidirectional"))
    )
    (net (code "32") (name "Net-(EPD_C12-Pad1)") (class "Default")
      (node (ref "EPD_C12") (pin "1") (pinfunction "1_1") (pintype "passive"))
      (node (ref "J1") (pin "24") (pinfunction "24_24") (pintype "bidirectional"))
    )
    (net (code "33") (name "Net-(IC1-CT)") (class "Default")
      (node (ref "C_DELAY") (pin "1") (pinfunction "1_1") (pintype "passive"))
      (node (ref "IC1") (pin "5") (pinfunction "CT_5") (pintype "bidirectional"))
    )
    (net (code "34") (name "Net-(J2-PadA5)") (class "Default")
      (node (ref "J2") (pin "A5") (pinfunction "A5_A5") (pintype "bidirectional"))
      (node (ref "R2-USB1") (pin "2") (pinfunction "2_2") (pintype "passive"))
    )
    (net (code "35") (name "Net-(J2-PadB5)") (class "Default")
      (node (ref "J2") (pin "B5") (pinfunction "B5_B5") (pintype "bidirectional"))
      (node (ref "R2-USB") (pin "1") (pinfunction "1_1") (pintype "passive"))
    )
    (net (code "36") (name "Net-(MCP73831-PROG)") (class "Default")
      (node (ref "MCP73831") (pin "5") (pinfunction "PROG_5") (pintype "input"))
      (node (ref "R2_BAT") (pin "2") (pinfunction "2_2") (pintype "passive"))
    )
    (net (code "37") (name "Net-(MCP73831-STAT)") (class "Default")
      (node (ref "MCP73831") (pin "1") (pinfunction "STAT_1") (pintype "output"))
      (node (ref "R1_BAT") (pin "1") (pinfunction "1_1") (pintype "passive"))
    )
    (net (code "38") (name "PREVGH") (class "Default")
      (node (ref "D5") (pin "2") (pinfunction "A_2") (pintype "bidirectional"))
      (node (ref "EPD_C9") (pin "1") (pinfunction "1_1") (pintype "passive"))
      (node (ref "J1") (pin "21") (pinfunction "21_21") (pintype "bidirectional"))
    )
    (net (code "39") (name "PREVGL") (class "Default")
      (node (ref "D4") (pin "2") (pinfunction "A_2") (pintype "bidirectional"))
      (node (ref "EPD_C11") (pin "1") (pinfunction "1_1") (pintype "passive"))
      (node (ref "J1") (pin "23") (pinfunction "23_23") (pintype "bidirectional"))
    )
    (net (code "40") (name "RESE") (class "Default")
      (node (ref "J1") (pin "3") (pinfunction "3_3") (pintype "bidirectional"))
      (node (ref "Q3") (pin "2") (pinfunction "S_2") (pintype "bidirectional"))
      (node (ref "R3") (pin "2") (pinfunction "2_2") (pintype "passive"))
    )
    (net (code "41") (name "RESE'") (class "Default")
      (node (ref "R2") (pin "2") (pinfunction "2_2") (pintype "passive"))
      (node (ref "R3") (pin "1") (pinfunction "1_1") (pintype "passive"))
      (node (ref "SJ1") (pin "2") (pinfunction "2_2") (pintype "passive"))
    )
    (net (code "42") (name "RESET") (class "Default")
      (node (ref "C5") (pin "1") (pinfunction "1_1") (pintype "passive"))
      (node (ref "IC1") (pin "1") (pinfunction "VOUT_1") (pintype "bidirectional"))
      (node (ref "RESET_BUTTON") (pin "3") (pinfunction "3_3") (pintype "passive"))
      (node (ref "RESET_BUTTON") (pin "4") (pinfunction "4_4") (pintype "passive"))
      (node (ref "R_RESET") (pin "1") (pinfunction "1_1") (pintype "passive"))
      (node (ref "U2") (pin "3") (pinfunction "EN_3") (pintype "input"))
    )
    (net (code "43") (name "RTC_RST") (class "Default")
      (node (ref "U2") (pin "16") (pinfunction "IO18_16") (pintype "bidirectional"))
      (node (ref "U3") (pin "4") (pinfunction "~{RST}_4") (pintype "input"))
    )
    (net (code "44") (name "RX") (class "Default")
      (node (ref "RX") (pin "TP") (pinfunction "TP_TP") (pintype "input"))
      (node (ref "U2") (pin "24") (pinfunction "RXD0/GPIO17_24") (pintype "bidirectional"))
    )
    (net (code "45") (name "SCK") (class "Default")
      (node (ref "D10") (pin "2") (pinfunction "2_2") (pintype "passive"))
      (node (ref "J1") (pin "13") (pinfunction "13_13") (pintype "bidirectional"))
      (node (ref "J4") (pin "P5") (pinfunction "CLK_P5") (pintype "bidirectional"))
      (node (ref "R6") (pin "1") (pinfunction "1_1") (pintype "passive"))
      (node (ref "SCK") (pin "TP") (pinfunction "TP_TP") (pintype "input"))
      (node (ref "U1") (pin "6") (pinfunction "CLK_6") (pintype "input"))
      (node (ref "U2") (pin "6") (pinfunction "IO6_6") (pintype "bidirectional"))
    )
    (net (code "46") (name "SCL") (class "Default")
      (node (ref "J3") (pin "1") (pinfunction "1_1") (pintype "power_in"))
      (node (ref "R2-PINH") (pin "1") (pinfunction "1_1") (pintype "passive"))
      (node (ref "SENSOR2") (pin "4") (pinfunction "SCK_4") (pintype "input"))
      (node (ref "U2") (pin "20") (pinfunction "IO22_20") (pintype "bidirectional"))
      (node (ref "U3") (pin "16") (pinfunction "SCL_16") (pintype "input"))
      (node (ref "U4") (pin "7") (pinfunction "SCL_7") (pintype "input"))
    )
    (net (code "47") (name "SDA") (class "Default")
      (node (ref "J3") (pin "2") (pinfunction "2_2") (pintype "power_in"))
      (node (ref "R1-PINH") (pin "1") (pinfunction "1_1") (pintype "passive"))
      (node (ref "SENSOR2") (pin "3") (pinfunction "SDI_3") (pintype "bidirectional"))
      (node (ref "U2") (pin "19") (pinfunction "IO21_19") (pintype "bidirectional"))
      (node (ref "U3") (pin "15") (pinfunction "SDA_15") (pintype "bidirectional"))
      (node (ref "U4") (pin "8") (pinfunction "SDA_8") (pintype "bidirectional"))
    )
    (net (code "48") (name "SRC") (class "Default")
      (node (ref "C4") (pin "2") (pinfunction "2_2") (pintype "passive"))
      (node (ref "D5") (pin "1") (pinfunction "K_1") (pintype "bidirectional"))
      (node (ref "L1") (pin "1") (pinfunction "1_1") (pintype "passive"))
      (node (ref "Q3") (pin "3") (pinfunction "D_3") (pintype "bidirectional"))
    )
    (net (code "49") (name "SS_SD") (class "Default")
      (node (ref "D8") (pin "2") (pinfunction "2_2") (pintype "passive"))
      (node (ref "J4") (pin "P2") (pinfunction "CD/DAT3_P2") (pintype "bidirectional"))
      (node (ref "R10") (pin "1") (pinfunction "1_1") (pintype "passive"))
      (node (ref "U2") (pin "4") (pinfunction "IO4_4") (pintype "bidirectional"))
    )
    (net (code "50") (name "TX") (class "Default")
      (node (ref "TX") (pin "TP") (pinfunction "TP_TP") (pintype "input"))
      (node (ref "U2") (pin "25") (pinfunction "TXD0/GPIO16_25") (pintype "bidirectional"))
    )
    (net (code "51") (name "USB_D+") (class "Default")
      (node (ref "D1") (pin "4") (pinfunction "I/O2_2_4") (pintype "bidirectional"))
      (node (ref "U2") (pin "14") (pinfunction "IO13_14") (pintype "bidirectional"))
    )
    (net (code "52") (name "USB_D-") (class "Default")
      (node (ref "D1") (pin "6") (pinfunction "I/O1_2_6") (pintype "bidirectional"))
      (node (ref "U2") (pin "13") (pinfunction "IO12_13") (pintype "bidirectional"))
    )
    (net (code "53") (name "VBAT") (class "Default")
      (node (ref "C2_BAT") (pin "1") (pinfunction "1_1") (pintype "passive"))
      (node (ref "MCP73831") (pin "3") (pinfunction "VBAT_3") (pintype "power_in"))
      (node (ref "Q1") (pin "3") (pinfunction "D_3") (pintype "bidirectional"))
      (node (ref "U4") (pin "2") (pinfunction "CELL_2") (pintype "power_in"))
      (node (ref "U4") (pin "3") (pinfunction "VDD_3") (pintype "power_in"))
      (node (ref "VBAT") (pin "TP") (pinfunction "TP_TP") (pintype "input"))
    )
    (net (code "54") (name "VBUS") (class "Default")
      (node (ref "C1_BAT") (pin "1") (pinfunction "1_1") (pintype "passive"))
      (node (ref "C4_USB") (pin "1") (pinfunction "1_1") (pintype "passive"))
      (node (ref "C5_USB") (pin "1") (pinfunction "1_1") (pintype "passive"))
      (node (ref "CHG_LED") (pin "A") (pinfunction "A_A") (pintype "passive"))
      (node (ref "D1") (pin "2") (pinfunction "GND_2") (pintype "bidirectional"))
      (node (ref "D2") (pin "2") (pinfunction "ANODE_2") (pintype "bidirectional"))
      (node (ref "MCP73831") (pin "4") (pinfunction "VIN_4") (pintype "power_in"))
      (node (ref "PFMF.050.1") (pin "2") (pinfunction "2_2") (pintype "passive"))
      (node (ref "Q1") (pin "1") (pinfunction "G_1") (pintype "bidirectional"))
      (node (ref "R1_PWRUSB") (pin "2") (pinfunction "2_2") (pintype "passive"))
      (node (ref "VBUS") (pin "TP") (pinfunction "TP_TP") (pintype "input"))
    )
    (net (code "55") (name "VRTC") (class "Default")
      (node (ref "C10_SUPERCAP") (pin "2") (pinfunction "2_2") (pintype "passive"))
      (node (ref "C8") (pin "1") (pinfunction "1_1") (pintype "passive"))
      (node (ref "R_CAPACITOR") (pin "2") (pinfunction "2_2") (pintype "passive"))
      (node (ref "U3") (pin "14") (pinfunction "VBAT_14") (pintype "power_in"))
    )
    (net (code "56") (name "VUSB") (class "Default")
      (node (ref "J2") (pin "A4") (pinfunction "A4_A4") (pintype "bidirectional"))
      (node (ref "J2") (pin "A9") (pinfunction "A9_A9") (pintype "bidirectional"))
      (node (ref "J2") (pin "B4") (pinfunction "B4_B4") (pintype "bidirectional"))
      (node (ref "J2") (pin "B9") (pinfunction "B9_B9") (pintype "bidirectional"))
      (node (ref "PFMF.050.1") (pin "1") (pinfunction "1_1") (pintype "passive"))
    )
    (net (code "57") (name "unconnected-(IC1-NC-Pad4)") (class "Default")
      (node (ref "IC1") (pin "4") (pinfunction "NC_4") (pintype "no_connect"))
    )
    (net (code "58") (name "unconnected-(IC4-NC-Pad4)") (class "Default")
      (node (ref "IC4") (pin "4") (pinfunction "NC_4") (pintype "no_connect"))
    )
    (net (code "59") (name "unconnected-(J1-Pad1)") (class "Default")
      (node (ref "J1") (pin "1") (pinfunction "1_1") (pintype "bidirectional"))
    )
    (net (code "60") (name "unconnected-(J1-Pad6)") (class "Default")
      (node (ref "J1") (pin "6") (pinfunction "6_6") (pintype "bidirectional"))
    )
    (net (code "61") (name "unconnected-(J1-Pad7)") (class "Default")
      (node (ref "J1") (pin "7") (pinfunction "7_7") (pintype "bidirectional"))
    )
    (net (code "62") (name "unconnected-(J2-PadA8)") (class "Default")
      (node (ref "J2") (pin "A8") (pinfunction "A8_A8") (pintype "bidirectional"))
    )
    (net (code "63") (name "unconnected-(J2-PadB8)") (class "Default")
      (node (ref "J2") (pin "B8") (pinfunction "B8_B8") (pintype "bidirectional"))
    )
    (net (code "64") (name "unconnected-(J4-DAT1-PadP8)") (class "Default")
      (node (ref "J4") (pin "P8") (pinfunction "DAT1_P8") (pintype "bidirectional"))
    )
    (net (code "65") (name "unconnected-(J4-DAT2-PadP1)") (class "Default")
      (node (ref "J4") (pin "P1") (pinfunction "DAT2_P1") (pintype "bidirectional"))
    )
    (net (code "66") (name "unconnected-(J4-DETECTION_1-PadS1)") (class "Default")
      (node (ref "J4") (pin "S1") (pinfunction "DETECTION_1_S1") (pintype "bidirectional"))
    )
    (net (code "67") (name "unconnected-(J4-DETECTION_2-PadS2)") (class "Default")
      (node (ref "J4") (pin "S2") (pinfunction "DETECTION_2_S2") (pintype "bidirectional"))
    )
    (net (code "68") (name "unconnected-(U2-NC-Pad22)") (class "Default")
      (node (ref "U2") (pin "22") (pinfunction "NC_22") (pintype "no_connect"))
    )
    (net (code "69") (name "unconnected-(U4-~{ALERT}-Pad5)") (class "Default")
      (node (ref "U4") (pin "5") (pinfunction "~{ALERT}_5") (pintype "output"))
    )
  )
)
